# module_slot.net
KiCad netlist of a schematic drawn in Altium Designer
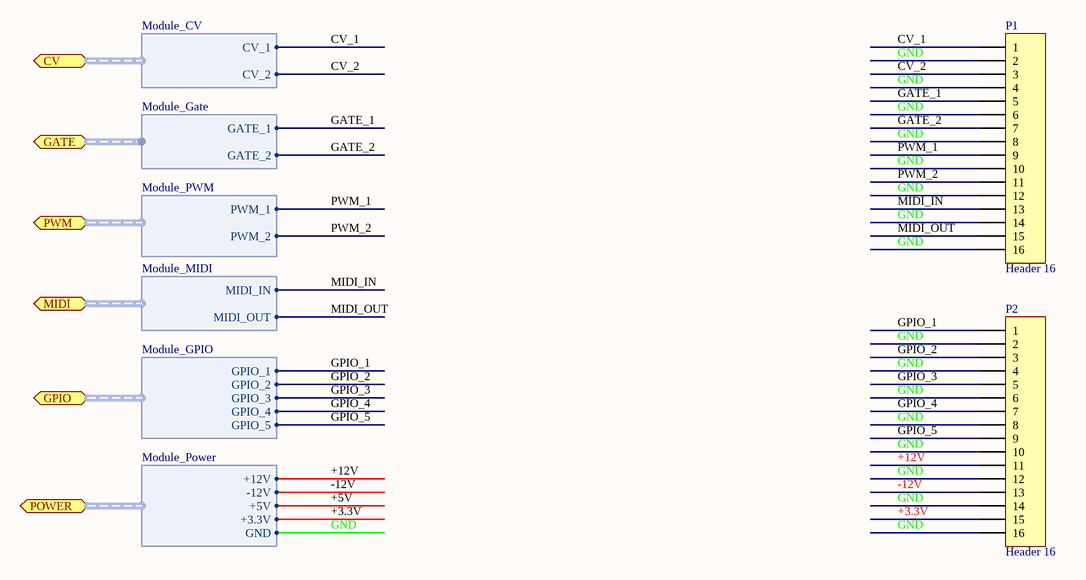
[diagram p0: module_slot.SchDoc]

(export (version "E")
  (design (tool "Eeschema 10.0.6"))
  (components
    (comp (ref "P1")
      (value "Header 16")
      (footprint "HDR1X16")
      (description "Header, 16-Pin")
      (fields (field (name "PUBLISHER") "Altium Limited"))
      (libsource (lib "Miscellaneous Connectors") (part "Header 16"))
    )
    (comp (ref "P2")
      (value "Header 16")
      (footprint "HDR1X16")
      (description "Header, 16-Pin")
      (fields (field (name "PUBLISHER") "Altium Limited"))
      (libsource (lib "Miscellaneous Connectors") (part "Header 16"))
    )
  )
  (nets
    (net (code "7") (name "/+3.3V") (class "Default")
      (node (ref "P2") (pin "15") (pinfunction "15_15") (pintype "passive"))
    )
    (net (code "9") (name "/+12V") (class "Default")
      (node (ref "P2") (pin "11") (pinfunction "11_11") (pintype "passive"))
    )
    (net (code "10") (name "/-12V") (class "Default")
      (node (ref "P2") (pin "13") (pinfunction "13_13") (pintype "passive"))
    )
    (net (code "11") (name "/CV_1") (class "Default")
      (node (ref "P1") (pin "1") (pinfunction "1_1") (pintype "passive"))
    )
    (net (code "12") (name "/CV_2") (class "Default")
      (node (ref "P1") (pin "3") (pinfunction "3_3") (pintype "passive"))
    )
    (net (code "13") (name "/GATE_1") (class "Default")
      (node (ref "P1") (pin "5") (pinfunction "5_5") (pintype "passive"))
    )
    (net (code "14") (name "/GATE_2") (class "Default")
      (node (ref "P1") (pin "7") (pinfunction "7_7") (pintype "passive"))
    )
    (net (code "15") (name "/GND") (class "Default")
      (node (ref "P1") (pin "10") (pinfunction "10_10") (pintype "passive"))
      (node (ref "P1") (pin "12") (pinfunction "12_12") (pintype "passive"))
      (node (ref "P1") (pin "14") (pinfunction "14_14") (pintype "passive"))
      (node (ref "P1") (pin "16") (pinfunction "16_16") (pintype "passive"))
      (node (ref "P1") (pin "2") (pinfunction "2_2") (pintype "passive"))
      (node (ref "P1") (pin "4") (pinfunction "4_4") (pintype "passive"))
      (node (ref "P1") (pin "6") (pinfunction "6_6") (pintype "passive"))
      (node (ref "P1") (pin "8") (pinfunction "8_8") (pintype "passive"))
      (node (ref "P2") (pin "10") (pinfunction "10_10") (pintype "passive"))
      (node (ref "P2") (pin "12") (pinfunction "12_12") (pintype "passive"))
      (node (ref "P2") (pin "14") (pinfunction "14_14") (pintype "passive"))
      (node (ref "P2") (pin "16") (pinfunction "16_16") (pintype "passive"))
      (node (ref "P2") (pin "2") (pinfunction "2_2") (pintype "passive"))
      (node (ref "P2") (pin "4") (pinfunction "4_4") (pintype "passive"))
      (node (ref "P2") (pin "6") (pinfunction "6_6") (pintype "passive"))
      (node (ref "P2") (pin "8") (pinfunction "8_8") (pintype "passive"))
    )
    (net (code "16") (name "/GPIO_1") (class "Default")
      (node (ref "P2") (pin "1") (pinfunction "1_1") (pintype "passive"))
    )
    (net (code "17") (name "/GPIO_2") (class "Default")
      (node (ref "P2") (pin "3") (pinfunction "3_3") (pintype "passive"))
    )
    (net (code "18") (name "/GPIO_3") (class "Default")
      (node (ref "P2") (pin "5") (pinfunction "5_5") (pintype "passive"))
    )
    (net (code "19") (name "/GPIO_4") (class "Default")
      (node (ref "P2") (pin "7") (pinfunction "7_7") (pintype "passive"))
    )
    (net (code "20") (name "/GPIO_5") (class "Default")
      (node (ref "P2") (pin "9") (pinfunction "9_9") (pintype "passive"))
    )
    (net (code "21") (name "/MIDI_IN") (class "Default")
      (node (ref "P1") (pin "13") (pinfunction "13_13") (pintype "passive"))
    )
    (net (code "22") (name "/MIDI_OUT") (class "Default")
      (node (ref "P1") (pin "15") (pinfunction "15_15") (pintype "passive"))
    )
    (net (code "23") (name "/PWM_1") (class "Default")
      (node (ref "P1") (pin "9") (pinfunction "9_9") (pintype "passive"))
    )
    (net (code "24") (name "/PWM_2") (class "Default")
      (node (ref "P1") (pin "11") (pinfunction "11_11") (pintype "passive"))
    )
  )
)
